# 2_-_FPGA.net
KiCad netlist of a schematic drawn in Altium Designer
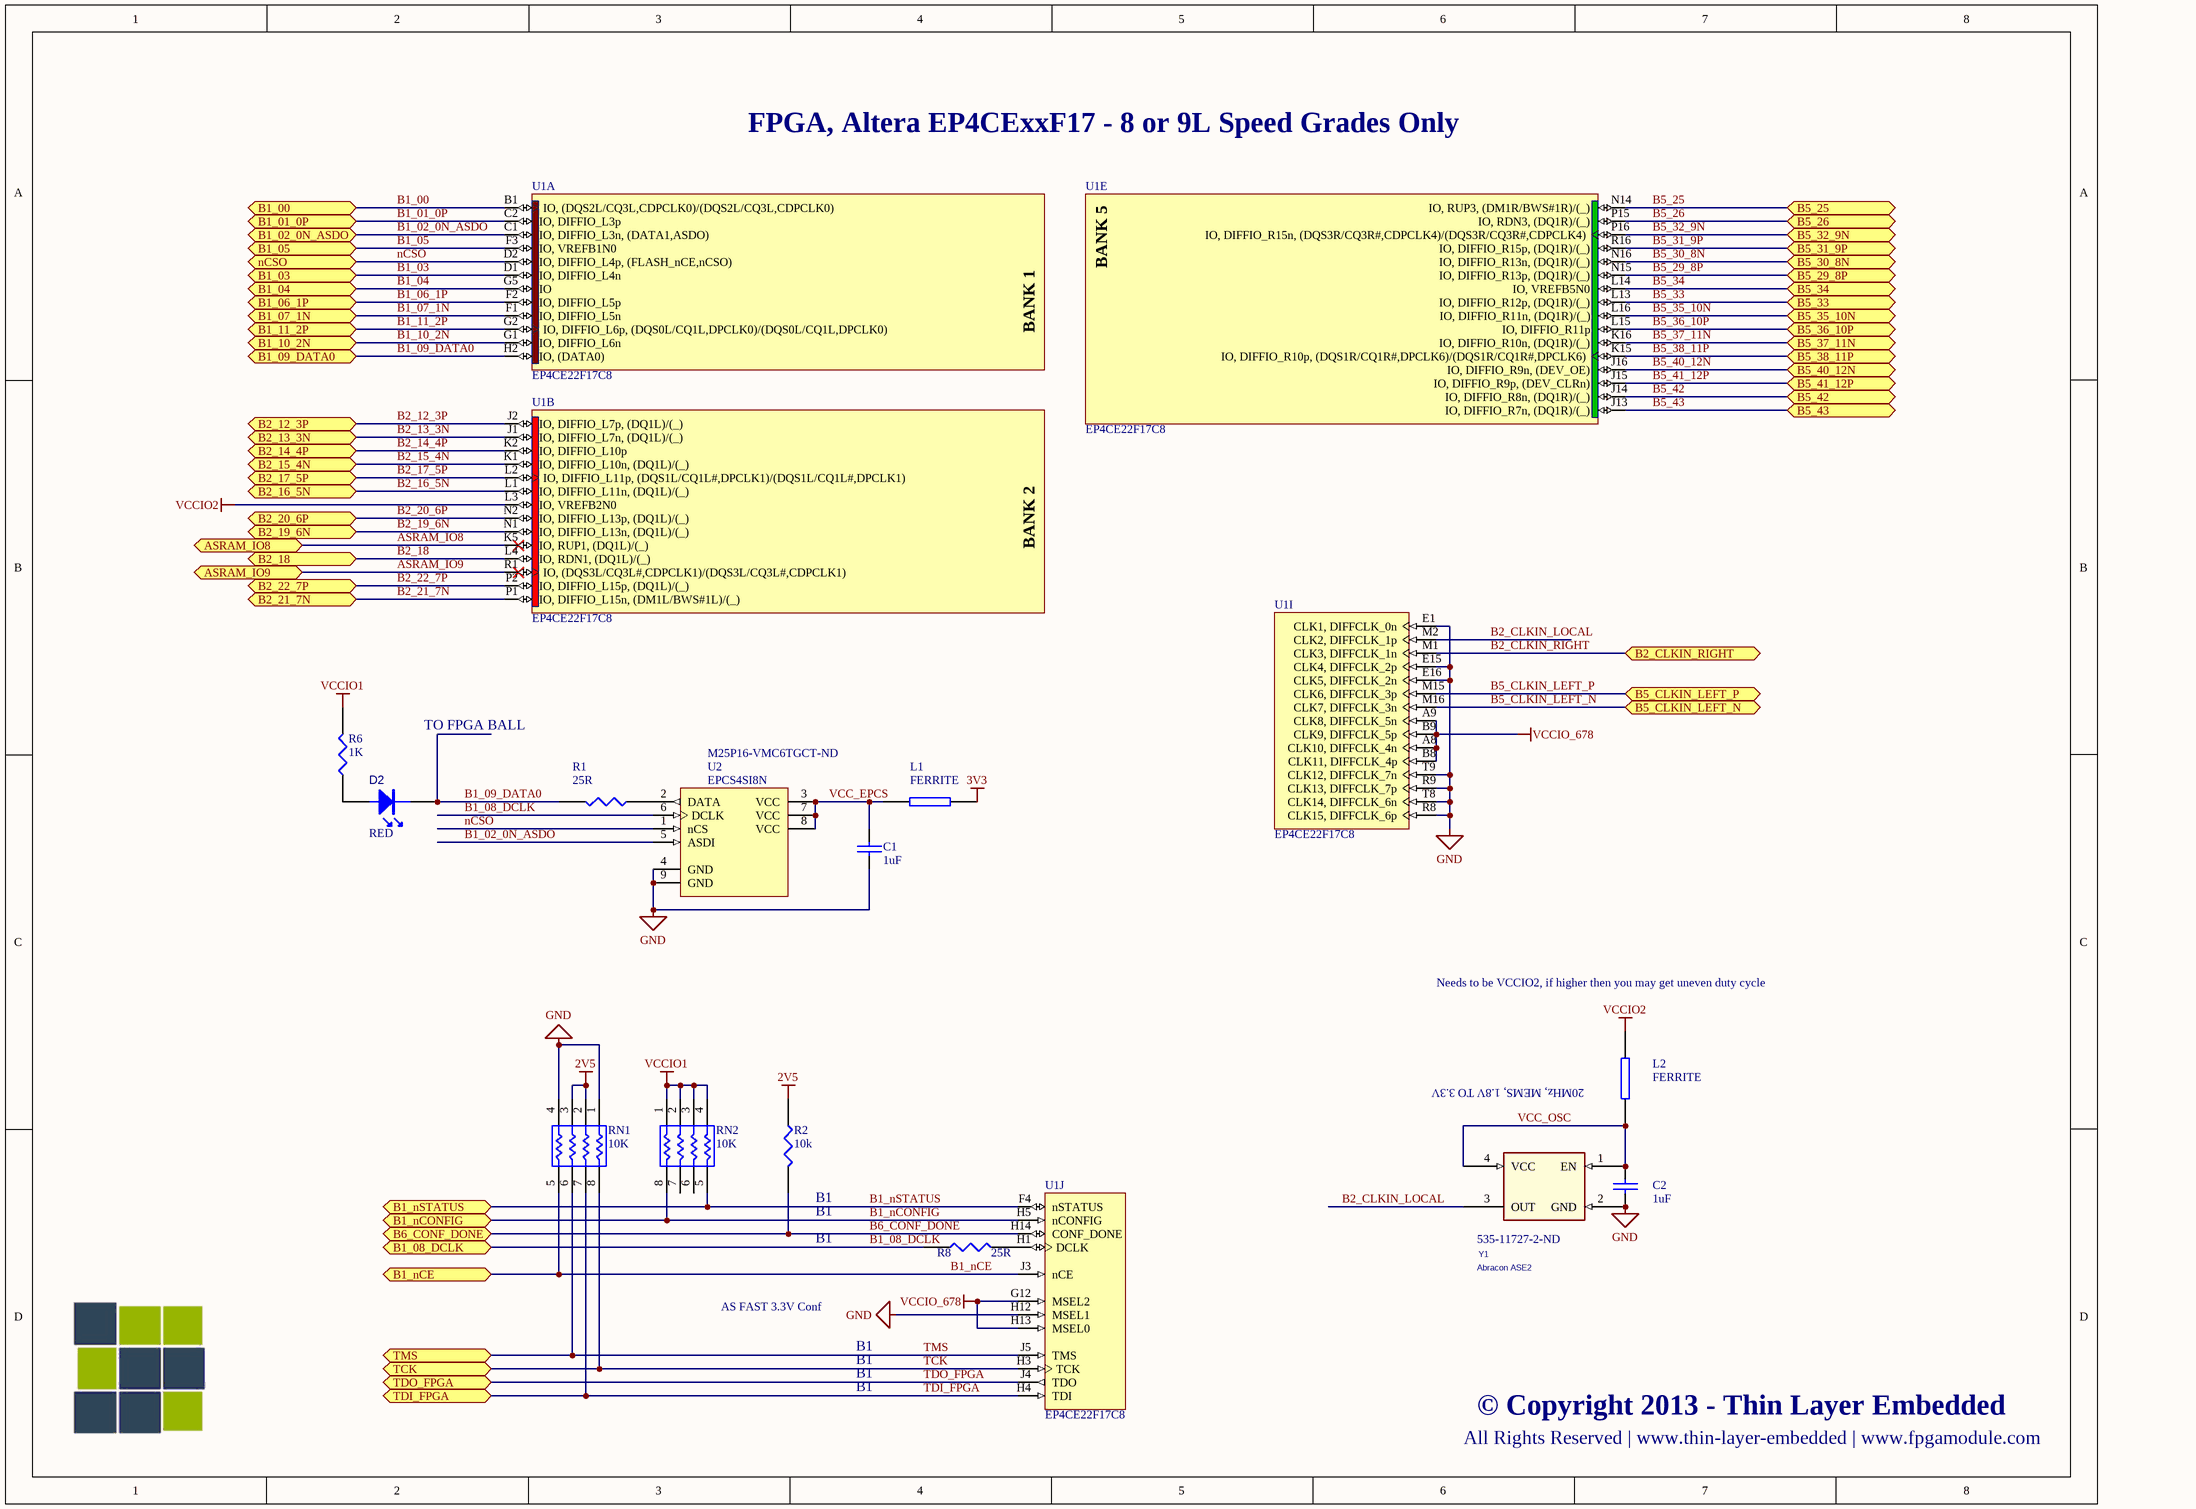
[diagram p0: 2 - FPGA.SchDoc]

(export (version "E")
  (design (tool "Eeschema 10.0.6"))
  (components
    (comp (ref "C1")
      (value "1uF")
      (footprint "0402_hd")
      (description "Capacitor")
      (libsource (lib "*") (part "CAP"))
    )
    (comp (ref "C2")
      (value "1uF")
      (footprint "0402_hd")
      (description "Capacitor")
      (libsource (lib "*") (part "CAP"))
    )
    (comp (ref "D2") (value "RED") (footprint "0402LED_HD") (libsource (lib "*") (part "LED")))
    (comp (ref "L1") (value "FERRITE") (footprint "0402_HD") (libsource (lib "") (part "FERRITE_1")))
    (comp (ref "L2")
      (value "FERRITE")
      (footprint "0402_HD")
      (libsource (lib "tea133-SCH-1") (part "FERRITE"))
    )
    (comp (ref "R1")
      (value "25R")
      (footprint "0402_HD")
      (description "RES 24.9 OHM 1/16W 1% 0402 SMD")
      (fields
        (field (name "MANUFACTURER") "Yageo")
        (field (name "MANUFACTURER PART NUMBER") "RC0402FR-0724R9L")
      )
      (libsource (lib "") (part "RES1_1"))
    )
    (comp (ref "R2")
      (value "10k")
      (footprint "0402_HD")
      (description "RES 24.9 OHM 1/16W 1% 0402 SMD")
      (fields
        (field (name "MANUFACTURER") "Yageo")
        (field (name "MANUFACTURER PART NUMBER") "RC0402FR-0724R9L")
      )
      (libsource (lib "*") (part "RES1"))
    )
    (comp (ref "R6") (value "1K") (footprint "0402_HD") (libsource (lib "*") (part "RES1")))
    (comp (ref "R8")
      (value "25R")
      (footprint "0402_HD")
      (description "RES 24.9 OHM 1/16W 1% 0402 SMD")
      (fields
        (field (name "MANUFACTURER") "Yageo")
        (field (name "MANUFACTURER PART NUMBER") "RC0402FR-0724R9L")
      )
      (libsource (lib "") (part "RES1_1"))
    )
    (comp (ref "RN1") (value "10K") (footprint "0402x4_hd") (libsource (lib "OB_1") (part "RESNET1")))
    (comp (ref "RN2") (value "10K") (footprint "0402x4_hd") (libsource (lib "OB_1") (part "RESNET1")))
    (comp (ref "U1")
      (value "EP4CE22F17C8")
      (footprint "FBGA256")
      (fields (field (name "PUBLISHER") "Altium Limited"))
      (libsource (lib "Altera Cyclone IV E") (part "EP4CE22F17C8"))
    )
    (comp (ref "U2")
      (value "EPCS4SI8N")
      (footprint "UFDFPN8_4X3")
      (description "IC SRL FLASH 16MBIT 75MHZ MLP8")
      (fields
        (field (name "SUPPLIER PART NUMBER 1") "M25P16-VMC6TGCT-ND")
        (field (name "MANUFACTURER") "Numonyx - A DIVISION OF MICRON SEMICONDUCTOR PRODUCTS, INC.")
        (field (name "MANUFACTURER PART NUMBER") "M25P16-VMC6TG")
        (field (name "PUBLISHER") "Altium Limited")
      )
      (libsource (lib "tea133-sch-2") (part "EPCS4SI8N"))
    )
    (comp (ref "Y1")
      (value "Abracon ASE2")
      (footprint "XTAL_ASDMB")
      (description "OSC - 50MHZ, +/-50PPM, 1.8V, CMOS CLOCK OSCILLATOR, SMD")
      (fields
        (field (name "MANUFACTURER PART NUM") "SM5545TEX-50.00M")
        (field (name "MANUFACTURER") "Pletronics")
        (field (name "SUPPLIER PART NUMBER 1") "535-11727-2-ND")
      )
      (libsource (lib "tea133-sch-2") (part "OSC_ALT"))
    )
  )
  (nets
    (net (code "1") (name "/ASRAM_IO8") (class "Default")
      (node (ref "U1") (pin "K5") (pinfunction "IO,_RUP1,_(DQ1L)/(_)_K5") (pintype "bidirectional"))
    )
    (net (code "2") (name "/ASRAM_IO9") (class "Default")
      (node (ref "U1") (pin "R1") (pinfunction "IO,_(DQS3L/CQ3L#,CDPCLK1)/(DQS3L/CQ3L#,CDPCLK1)_R1") (pintype "bidirectional"))
    )
    (net (code "3") (name "/B1_00") (class "Default")
      (node (ref "U1") (pin "B1") (pinfunction "IO,_(DQS2L/CQ3L,CDPCLK0)/(DQS2L/CQ3L,CDPCLK0)_B1") (pintype "bidirectional"))
    )
    (net (code "4") (name "/B1_01_0P") (class "Default")
      (node (ref "U1") (pin "C2") (pinfunction "IO,_DIFFIO_L3p_C2") (pintype "bidirectional"))
    )
    (net (code "5") (name "/B1_02_0N_ASDO") (class "Default")
      (node (ref "U1") (pin "C1") (pinfunction "IO,_DIFFIO_L3n,_(DATA1,ASDO)_C1") (pintype "bidirectional"))
      (node (ref "U2") (pin "5") (pinfunction "ASDI_5") (pintype "input"))
    )
    (net (code "6") (name "/B1_03") (class "Default")
      (node (ref "U1") (pin "D1") (pinfunction "IO,_DIFFIO_L4n_D1") (pintype "bidirectional"))
    )
    (net (code "7") (name "/B1_04") (class "Default")
      (node (ref "U1") (pin "G5") (pinfunction "IO_G5") (pintype "bidirectional"))
    )
    (net (code "8") (name "/B1_05") (class "Default")
      (node (ref "U1") (pin "F3") (pinfunction "IO,_VREFB1N0_F3") (pintype "bidirectional"))
    )
    (net (code "9") (name "/B1_06_1P") (class "Default")
      (node (ref "U1") (pin "F2") (pinfunction "IO,_DIFFIO_L5p_F2") (pintype "bidirectional"))
    )
    (net (code "10") (name "/B1_07_1N") (class "Default")
      (node (ref "U1") (pin "F1") (pinfunction "IO,_DIFFIO_L5n_F1") (pintype "bidirectional"))
    )
    (net (code "11") (name "/B1_08_DCLK") (class "Default")
      (node (ref "R8") (pin "1") (pinfunction "1_1") (pintype "passive"))
      (node (ref "U2") (pin "6") (pinfunction "DCLK_6") (pintype "input"))
    )
    (net (code "12") (name "/B1_09_DATA0") (class "Default")
      (node (ref "D2") (pin "K") (pinfunction "2_K") (pintype "passive"))
      (node (ref "R1") (pin "1") (pinfunction "1_1") (pintype "passive"))
      (node (ref "U1") (pin "H2") (pinfunction "IO,_(DATA0)_H2") (pintype "bidirectional"))
    )
    (net (code "13") (name "/B1_10_2N") (class "Default")
      (node (ref "U1") (pin "G1") (pinfunction "IO,_DIFFIO_L6n_G1") (pintype "bidirectional"))
    )
    (net (code "14") (name "/B1_11_2P") (class "Default")
      (node (ref "U1") (pin "G2") (pinfunction "IO,_DIFFIO_L6p,_(DQS0L/CQ1L,DPCLK0)/(DQS0L/CQ1L,DPCLK0)_G2") (pintype "bidirectional"))
    )
    (net (code "15") (name "/B1_nCE") (class "Default")
      (node (ref "RN1") (pin "5") (pinfunction "5_5") (pintype "passive"))
      (node (ref "U1") (pin "J3") (pinfunction "nCE_J3") (pintype "input"))
    )
    (net (code "16") (name "/B1_nCONFIG") (class "Default")
      (node (ref "RN2") (pin "8") (pinfunction "8_8") (pintype "passive"))
      (node (ref "U1") (pin "H5") (pinfunction "nCONFIG_H5") (pintype "input"))
    )
    (net (code "17") (name "/B1_nSTATUS") (class "Default")
      (node (ref "RN2") (pin "5") (pinfunction "5_5") (pintype "passive"))
      (node (ref "U1") (pin "F4") (pinfunction "nSTATUS_F4") (pintype "bidirectional"))
    )
    (net (code "18") (name "/B2_12_3P") (class "Default")
      (node (ref "U1") (pin "J2") (pinfunction "IO,_DIFFIO_L7p,_(DQ1L)/(_)_J2") (pintype "bidirectional"))
    )
    (net (code "19") (name "/B2_13_3N") (class "Default")
      (node (ref "U1") (pin "J1") (pinfunction "IO,_DIFFIO_L7n,_(DQ1L)/(_)_J1") (pintype "bidirectional"))
    )
    (net (code "20") (name "/B2_14_4P") (class "Default")
      (node (ref "U1") (pin "K2") (pinfunction "IO,_DIFFIO_L10p_K2") (pintype "bidirectional"))
    )
    (net (code "21") (name "/B2_15_4N") (class "Default")
      (node (ref "U1") (pin "K1") (pinfunction "IO,_DIFFIO_L10n,_(DQ1L)/(_)_K1") (pintype "bidirectional"))
    )
    (net (code "22") (name "/B2_16_5N") (class "Default")
      (node (ref "U1") (pin "L1") (pinfunction "IO,_DIFFIO_L11n,_(DQ1L)/(_)_L1") (pintype "bidirectional"))
    )
    (net (code "23") (name "/B2_17_5P") (class "Default")
      (node (ref "U1") (pin "L2") (pinfunction "IO,_DIFFIO_L11p,_(DQS1L/CQ1L#,DPCLK1)/(DQS1L/CQ1L#,DPCLK1)_L2") (pintype "bidirectional"))
    )
    (net (code "24") (name "/B2_18") (class "Default")
      (node (ref "U1") (pin "L4") (pinfunction "IO,_RDN1,_(DQ1L)/(_)_L4") (pintype "bidirectional"))
    )
    (net (code "25") (name "/B2_19_6N") (class "Default")
      (node (ref "U1") (pin "N1") (pinfunction "IO,_DIFFIO_L13n,_(DQ1L)/(_)_N1") (pintype "bidirectional"))
    )
    (net (code "26") (name "/B2_20_6P") (class "Default")
      (node (ref "U1") (pin "N2") (pinfunction "IO,_DIFFIO_L13p,_(DQ1L)/(_)_N2") (pintype "bidirectional"))
    )
    (net (code "27") (name "/B2_21_7N") (class "Default")
      (node (ref "U1") (pin "P1") (pinfunction "IO,_DIFFIO_L15n,_(DM1L/BWS#1L)/(_)_P1") (pintype "bidirectional"))
    )
    (net (code "28") (name "/B2_22_7P") (class "Default")
      (node (ref "U1") (pin "P2") (pinfunction "IO,_DIFFIO_L15p,_(DQ1L)/(_)_P2") (pintype "bidirectional"))
    )
    (net (code "29") (name "/B2_CLKIN_LOCAL") (class "Default")
      (node (ref "U1") (pin "M2") (pinfunction "CLK2,_DIFFCLK_1p_M2") (pintype "input"))
      (node (ref "Y1") (pin "3") (pinfunction "OUT_3") (pintype "passive"))
    )
    (net (code "30") (name "/B2_CLKIN_RIGHT") (class "Default")
      (node (ref "U1") (pin "M1") (pinfunction "CLK3,_DIFFCLK_1n_M1") (pintype "input"))
    )
    (net (code "31") (name "/B5_25") (class "Default")
      (node (ref "U1") (pin "N14") (pinfunction "IO,_RUP3,_(DM1R/BWS#1R)/(_)_N14") (pintype "bidirectional"))
    )
    (net (code "32") (name "/B5_26") (class "Default")
      (node (ref "U1") (pin "P15") (pinfunction "IO,_RDN3,_(DQ1R)/(_)_P15") (pintype "bidirectional"))
    )
    (net (code "33") (name "/B5_29_8P") (class "Default")
      (node (ref "U1") (pin "N15") (pinfunction "IO,_DIFFIO_R13p,_(DQ1R)/(_)_N15") (pintype "bidirectional"))
    )
    (net (code "34") (name "/B5_30_8N") (class "Default")
      (node (ref "U1") (pin "N16") (pinfunction "IO,_DIFFIO_R13n,_(DQ1R)/(_)_N16") (pintype "bidirectional"))
    )
    (net (code "35") (name "/B5_31_9P") (class "Default")
      (node (ref "U1") (pin "R16") (pinfunction "IO,_DIFFIO_R15p,_(DQ1R)/(_)_R16") (pintype "bidirectional"))
    )
    (net (code "36") (name "/B5_32_9N") (class "Default")
      (node (ref "U1") (pin "P16") (pinfunction "IO,_DIFFIO_R15n,_(DQS3R/CQ3R#,CDPCLK4)/(DQS3R/CQ3R#,CDPCLK4)_P16") (pintype "bidirectional"))
    )
    (net (code "37") (name "/B5_33") (class "Default")
      (node (ref "U1") (pin "L13") (pinfunction "IO,_DIFFIO_R12p,_(DQ1R)/(_)_L13") (pintype "bidirectional"))
    )
    (net (code "38") (name "/B5_34") (class "Default")
      (node (ref "U1") (pin "L14") (pinfunction "IO,_VREFB5N0_L14") (pintype "bidirectional"))
    )
    (net (code "39") (name "/B5_35_10N") (class "Default")
      (node (ref "U1") (pin "L16") (pinfunction "IO,_DIFFIO_R11n,_(DQ1R)/(_)_L16") (pintype "bidirectional"))
    )
    (net (code "40") (name "/B5_36_10P") (class "Default")
      (node (ref "U1") (pin "L15") (pinfunction "IO,_DIFFIO_R11p_L15") (pintype "bidirectional"))
    )
    (net (code "41") (name "/B5_37_11N") (class "Default")
      (node (ref "U1") (pin "K16") (pinfunction "IO,_DIFFIO_R10n,_(DQ1R)/(_)_K16") (pintype "bidirectional"))
    )
    (net (code "42") (name "/B5_38_11P") (class "Default")
      (node (ref "U1") (pin "K15") (pinfunction "IO,_DIFFIO_R10p,_(DQS1R/CQ1R#,DPCLK6)/(DQS1R/CQ1R#,DPCLK6)_K15") (pintype "bidirectional"))
    )
    (net (code "43") (name "/B5_40_12N") (class "Default")
      (node (ref "U1") (pin "J16") (pinfunction "IO,_DIFFIO_R9n,_(DEV_OE)_J16") (pintype "bidirectional"))
    )
    (net (code "44") (name "/B5_41_12P") (class "Default")
      (node (ref "U1") (pin "J15") (pinfunction "IO,_DIFFIO_R9p,_(DEV_CLRn)_J15") (pintype "bidirectional"))
    )
    (net (code "45") (name "/B5_42") (class "Default")
      (node (ref "U1") (pin "J14") (pinfunction "IO,_DIFFIO_R8n,_(DQ1R)/(_)_J14") (pintype "bidirectional"))
    )
    (net (code "46") (name "/B5_43") (class "Default")
      (node (ref "U1") (pin "J13") (pinfunction "IO,_DIFFIO_R7n,_(DQ1R)/(_)_J13") (pintype "bidirectional"))
    )
    (net (code "47") (name "/B5_CLKIN_LEFT_N") (class "Default")
      (node (ref "U1") (pin "M16") (pinfunction "CLK7,_DIFFCLK_3n_M16") (pintype "input"))
    )
    (net (code "48") (name "/B5_CLKIN_LEFT_P") (class "Default")
      (node (ref "U1") (pin "M15") (pinfunction "CLK6,_DIFFCLK_3p_M15") (pintype "input"))
    )
    (net (code "49") (name "/B6_CONF_DONE") (class "Default")
      (node (ref "R2") (pin "1") (pinfunction "1_1") (pintype "passive"))
      (node (ref "U1") (pin "H14") (pinfunction "CONF_DONE_H14") (pintype "bidirectional"))
    )
    (net (code "50") (name "/TCK") (class "Default")
      (node (ref "RN1") (pin "8") (pinfunction "8_8") (pintype "passive"))
      (node (ref "U1") (pin "H3") (pinfunction "TCK_H3") (pintype "input"))
    )
    (net (code "51") (name "/TDI_FPGA") (class "Default")
      (node (ref "RN1") (pin "7") (pinfunction "17_7") (pintype "passive"))
      (node (ref "U1") (pin "H4") (pinfunction "TDI_H4") (pintype "input"))
    )
    (net (code "52") (name "/TDO_FPGA") (class "Default")
      (node (ref "U1") (pin "J4") (pinfunction "TDO_J4") (pintype "output"))
    )
    (net (code "53") (name "/TMS") (class "Default")
      (node (ref "RN1") (pin "6") (pinfunction "6_6") (pintype "passive"))
      (node (ref "U1") (pin "J5") (pinfunction "TMS_J5") (pintype "input"))
    )
    (net (code "54") (name "/VCC_EPCS") (class "Default")
      (node (ref "C1") (pin "1") (pinfunction "1_1") (pintype "passive"))
      (node (ref "L1") (pin "1") (pinfunction "1_1") (pintype "passive"))
      (node (ref "U2") (pin "3") (pinfunction "VCC_3") (pintype "power_in"))
      (node (ref "U2") (pin "7") (pinfunction "VCC_7") (pintype "power_in"))
      (node (ref "U2") (pin "8") (pinfunction "VCC_8") (pintype "power_in"))
    )
    (net (code "55") (name "/VCC_OSC") (class "Default")
      (node (ref "C2") (pin "1") (pinfunction "1_1") (pintype "passive"))
      (node (ref "L2") (pin "1") (pinfunction "1_1") (pintype "passive"))
      (node (ref "Y1") (pin "1") (pinfunction "EN_1") (pintype "input"))
      (node (ref "Y1") (pin "4") (pinfunction "VCC_4") (pintype "input"))
    )
    (net (code "56") (name "/nCSO") (class "Default")
      (node (ref "U1") (pin "D2") (pinfunction "IO,_DIFFIO_L4p,_(FLASH_nCE,nCSO)_D2") (pintype "bidirectional"))
      (node (ref "U2") (pin "1") (pinfunction "nCS_1") (pintype "input"))
    )
    (net (code "57") (name "2V5") (class "Default")
      (node (ref "R2") (pin "2") (pinfunction "2_2") (pintype "passive"))
      (node (ref "RN1") (pin "2") (pinfunction "2_2") (pintype "passive"))
      (node (ref "RN1") (pin "3") (pinfunction "3_3") (pintype "passive"))
    )
    (net (code "58") (name "3V3") (class "Default")
      (node (ref "L1") (pin "2") (pinfunction "2_2") (pintype "passive"))
    )
    (net (code "59") (name "GND") (class "Default")
      (node (ref "C1") (pin "2") (pinfunction "2_2") (pintype "passive"))
      (node (ref "C2") (pin "2") (pinfunction "2_2") (pintype "passive"))
      (node (ref "RN1") (pin "1") (pinfunction "1_1") (pintype "passive"))
      (node (ref "RN1") (pin "4") (pinfunction "4_4") (pintype "passive"))
      (node (ref "U1") (pin "E1") (pinfunction "CLK1,_DIFFCLK_0n_E1") (pintype "input"))
      (node (ref "U1") (pin "E15") (pinfunction "CLK4,_DIFFCLK_2p_E15") (pintype "input"))
      (node (ref "U1") (pin "E16") (pinfunction "CLK5,_DIFFCLK_2n_E16") (pintype "input"))
      (node (ref "U1") (pin "H12") (pinfunction "MSEL1_H12") (pintype "input"))
      (node (ref "U1") (pin "R8") (pinfunction "CLK15,_DIFFCLK_6p_R8") (pintype "input"))
      (node (ref "U1") (pin "R9") (pinfunction "CLK13,_DIFFCLK_7p_R9") (pintype "input"))
      (node (ref "U1") (pin "T8") (pinfunction "CLK14,_DIFFCLK_6n_T8") (pintype "input"))
      (node (ref "U1") (pin "T9") (pinfunction "CLK12,_DIFFCLK_7n_T9") (pintype "input"))
      (node (ref "U2") (pin "4") (pinfunction "GND_4") (pintype "power_in"))
      (node (ref "U2") (pin "9") (pinfunction "GND_9") (pintype "passive"))
      (node (ref "Y1") (pin "2") (pinfunction "GND_2") (pintype "input"))
    )
    (net (code "60") (name "Net-(D2-1)") (class "Default")
      (node (ref "D2") (pin "A") (pinfunction "1_A") (pintype "passive"))
      (node (ref "R6") (pin "2") (pinfunction "2_2") (pintype "passive"))
    )
    (net (code "61") (name "Net-(U1J-DCLK)") (class "Default")
      (node (ref "R8") (pin "2") (pinfunction "2_2") (pintype "passive"))
      (node (ref "U1") (pin "H1") (pinfunction "DCLK_H1") (pintype "bidirectional"))
    )
    (net (code "62") (name "Net-(U2-DATA)") (class "Default")
      (node (ref "R1") (pin "2") (pinfunction "2_2") (pintype "passive"))
      (node (ref "U2") (pin "2") (pinfunction "DATA_2") (pintype "output"))
    )
    (net (code "63") (name "VCCIO1") (class "Default")
      (node (ref "R6") (pin "1") (pinfunction "1_1") (pintype "passive"))
      (node (ref "RN2") (pin "1") (pinfunction "1_1") (pintype "passive"))
      (node (ref "RN2") (pin "2") (pinfunction "2_2") (pintype "passive"))
      (node (ref "RN2") (pin "3") (pinfunction "3_3") (pintype "passive"))
      (node (ref "RN2") (pin "4") (pinfunction "4_4") (pintype "passive"))
    )
    (net (code "64") (name "VCCIO2") (class "Default")
      (node (ref "L2") (pin "2") (pinfunction "2_2") (pintype "passive"))
      (node (ref "U1") (pin "L3") (pinfunction "IO,_VREFB2N0_L3") (pintype "bidirectional"))
    )
    (net (code "65") (name "VCCIO_678") (class "Default")
      (node (ref "U1") (pin "A8") (pinfunction "CLK10,_DIFFCLK_4n_A8") (pintype "input"))
      (node (ref "U1") (pin "A9") (pinfunction "CLK8,_DIFFCLK_5n_A9") (pintype "input"))
      (node (ref "U1") (pin "B8") (pinfunction "CLK11,_DIFFCLK_4p_B8") (pintype "input"))
      (node (ref "U1") (pin "B9") (pinfunction "CLK9,_DIFFCLK_5p_B9") (pintype "input"))
      (node (ref "U1") (pin "G12") (pinfunction "MSEL2_G12") (pintype "input"))
      (node (ref "U1") (pin "H13") (pinfunction "MSEL0_H13") (pintype "input"))
    )
    (net (code "66") (name "unconnected-(RN2-17-Pad7)") (class "Default")
      (node (ref "RN2") (pin "7") (pinfunction "17_7") (pintype "passive"))
    )
    (net (code "67") (name "unconnected-(RN2-Pad6)") (class "Default")
      (node (ref "RN2") (pin "6") (pinfunction "6_6") (pintype "passive"))
    )
  )
)
